# buckconvertervrs.net
KiCad netlist of a schematic drawn in EAGLE
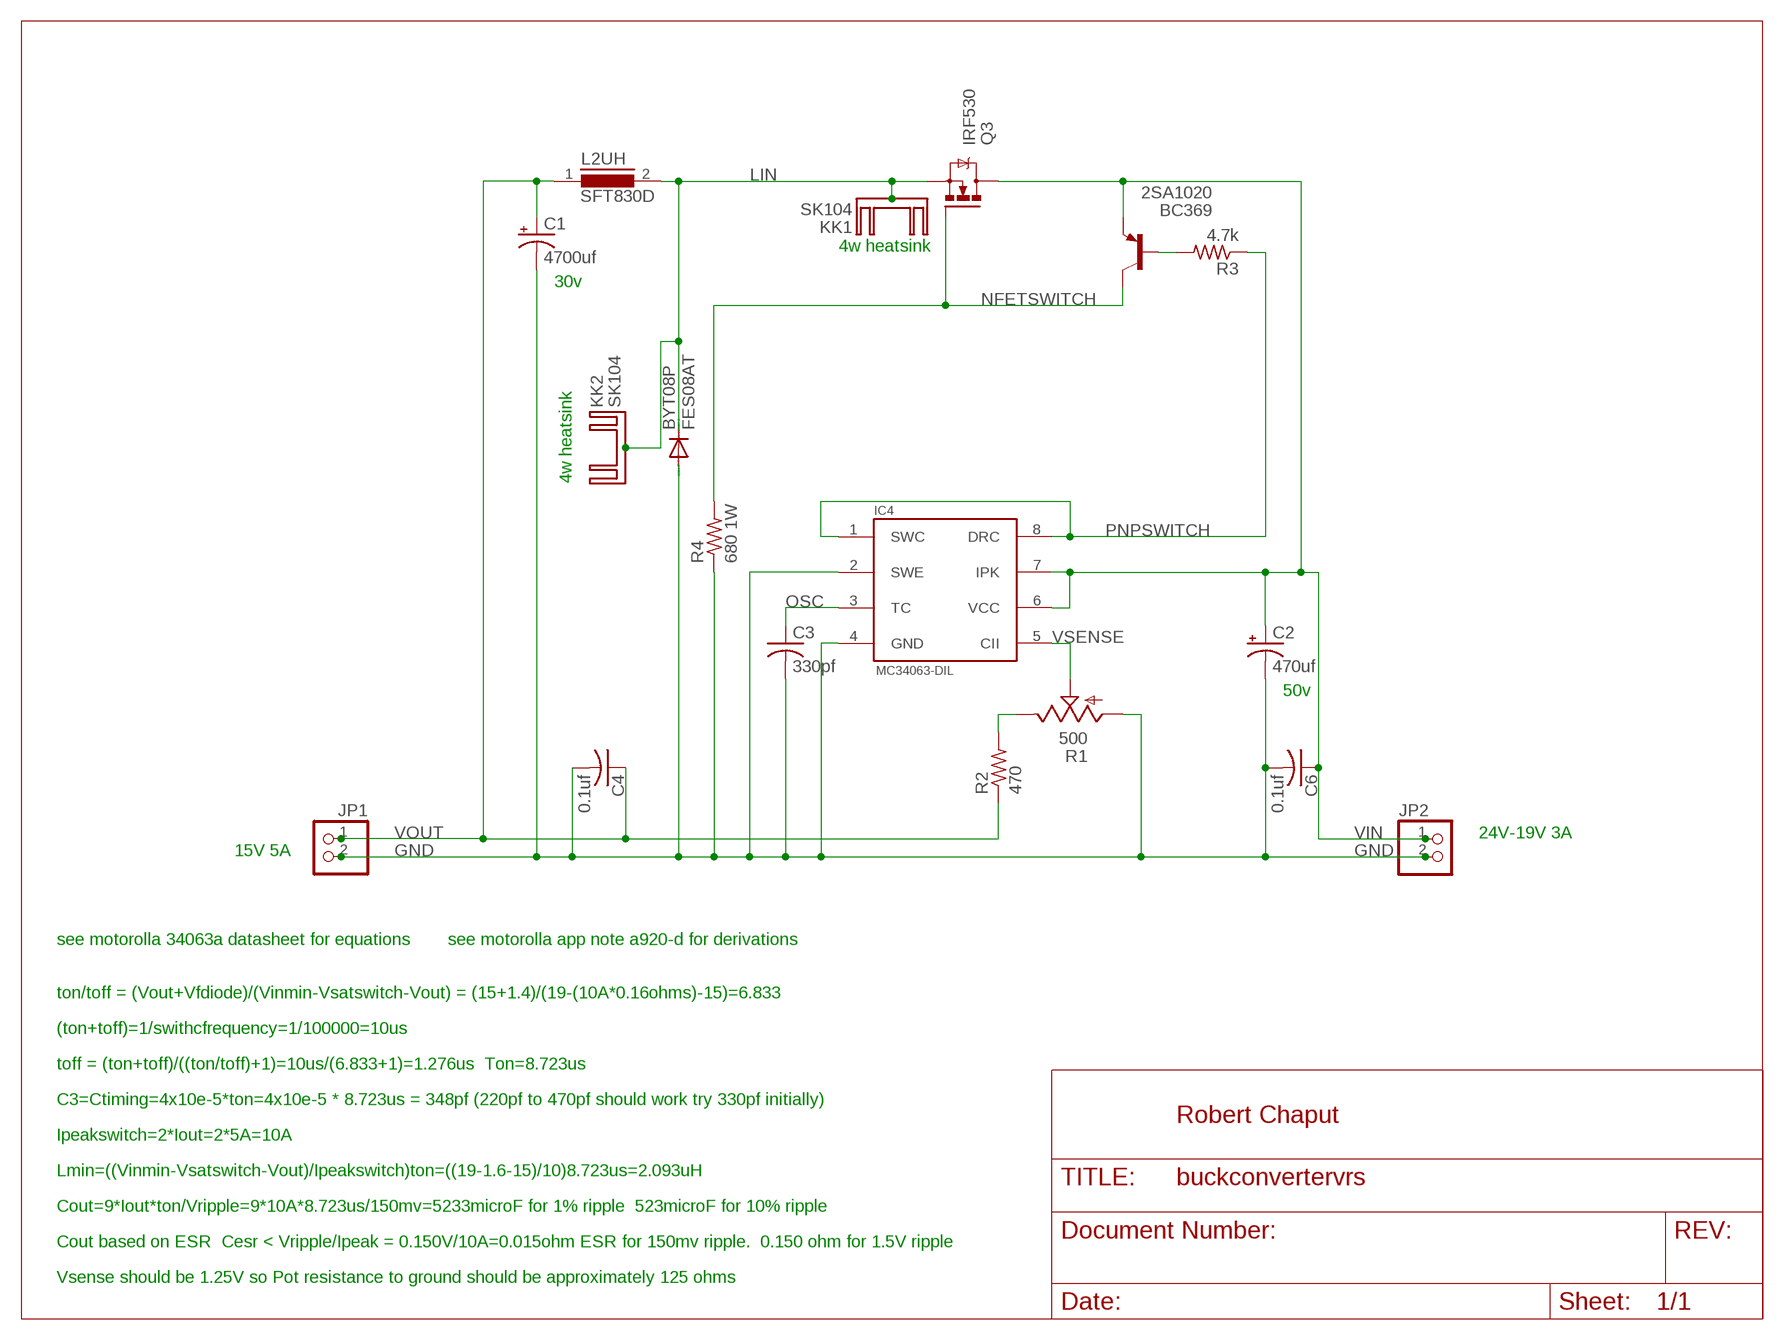
[diagram p0: schematic, sheet 1]

(export (version "E")
  (design (tool "Eeschema 10.0.6"))
  (components
    (comp (ref "2SA1020")
      (value "BC369")
      (footprint "eagle-import:TO92-BCE")
      (libsource (lib "eagle-import") (part "BC369"))
    )
    (comp (ref "BYT08P")
      (value "FES08AT")
      (footprint "eagle-import:DO220S")
      (libsource (lib "eagle-import") (part "FES08AT"))
    )
    (comp (ref "C1")
      (value "4700uf")
      (footprint "eagle-import:EB30D")
      (libsource (lib "eagle-import") (part "CPOL-USE10-30"))
    )
    (comp (ref "C2")
      (value "470uf")
      (footprint "eagle-import:E5-8,5")
      (libsource (lib "eagle-import") (part "CPOL-USE5-8.5"))
    )
    (comp (ref "C3")
      (value "330pf")
      (footprint "eagle-import:C050-030X075")
      (libsource (lib "eagle-import") (part "C-US050-030X075"))
    )
    (comp (ref "C4")
      (value "0.1uf")
      (footprint "eagle-import:C050-030X075")
      (libsource (lib "eagle-import") (part "C-US050-030X075"))
    )
    (comp (ref "C6")
      (value "0.1uf")
      (footprint "eagle-import:C050-030X075")
      (libsource (lib "eagle-import") (part "C-US050-030X075"))
    )
    (comp (ref "IC4")
      (value "MC34063-DIL")
      (footprint "eagle-import:DIL08")
      (libsource (lib "eagle-import") (part "MC34063-DIL"))
    )
    (comp (ref "JP1")
      (value "PINHD-1X2")
      (footprint "eagle-import:1X02")
      (libsource (lib "eagle-import") (part "PINHD-1X2"))
    )
    (comp (ref "JP2")
      (value "PINHD-1X2")
      (footprint "eagle-import:1X02")
      (libsource (lib "eagle-import") (part "PINHD-1X2"))
    )
    (comp (ref "KK1")
      (value "SK104")
      (footprint "eagle-import:SK104")
      (libsource (lib "eagle-import") (part "SK104"))
    )
    (comp (ref "KK2")
      (value "SK104")
      (footprint "eagle-import:SK104")
      (libsource (lib "eagle-import") (part "SK104"))
    )
    (comp (ref "L2UH")
      (value "SFT830D")
      (footprint "eagle-import:SFT830D")
      (libsource (lib "eagle-import") (part "SFT830D"))
    )
    (comp (ref "Q3")
      (value "IRF530")
      (footprint "eagle-import:TO220BV")
      (libsource (lib "eagle-import") (part "IRF530"))
    )
    (comp (ref "R1")
      (value "500")
      (footprint "eagle-import:PT-SPIN")
      (libsource (lib "eagle-import") (part "TRIM_US-PTSPIN"))
    )
    (comp (ref "R2")
      (value "470")
      (footprint "eagle-import:0309V")
      (libsource (lib "eagle-import") (part "R-US_0309/V"))
    )
    (comp (ref "R3")
      (value "4.7k")
      (footprint "eagle-import:0309V")
      (libsource (lib "eagle-import") (part "R-US_0309/V"))
    )
    (comp (ref "R4")
      (value "680 1W")
      (footprint "eagle-import:P0613V")
      (libsource (lib "eagle-import") (part "R-US_0613/5V"))
    )
  )
  (nets
    (net (code "1") (name "/GND") (class "Default")
      (node (ref "BYT08P") (pin "A") (pinfunction "A_A") (pintype "passive"))
      (node (ref "C1") (pin "-") (pinfunction "-_-") (pintype "passive"))
      (node (ref "C2") (pin "-") (pinfunction "-_-") (pintype "passive"))
      (node (ref "C3") (pin "2") (pinfunction "2_2") (pintype "passive"))
      (node (ref "C4") (pin "2") (pinfunction "2_2") (pintype "passive"))
      (node (ref "C6") (pin "2") (pinfunction "2_2") (pintype "passive"))
      (node (ref "IC4") (pin "2") (pinfunction "SWE_2") (pintype "bidirectional"))
      (node (ref "IC4") (pin "4") (pinfunction "GND_4") (pintype "power_in"))
      (node (ref "JP1") (pin "2") (pinfunction "2_2") (pintype "passive"))
      (node (ref "JP2") (pin "2") (pinfunction "2_2") (pintype "passive"))
      (node (ref "R1") (pin "A") (pinfunction "A_A") (pintype "passive"))
      (node (ref "R4") (pin "1") (pinfunction "1_1") (pintype "passive"))
    )
    (net (code "2") (name "/LIN") (class "Default")
      (node (ref "BYT08P") (pin "C") (pinfunction "C_C") (pintype "passive"))
      (node (ref "L2UH") (pin "2") (pinfunction "2_2") (pintype "passive"))
      (node (ref "Q3") (pin "S") (pinfunction "S_S") (pintype "passive"))
    )
    (net (code "3") (name "/NFETSWITCH") (class "Default")
      (node (ref "2SA1020") (pin "C") (pinfunction "C_C") (pintype "passive"))
      (node (ref "Q3") (pin "G") (pinfunction "G_G") (pintype "passive"))
      (node (ref "R4") (pin "2") (pinfunction "2_2") (pintype "passive"))
    )
    (net (code "4") (name "/OSC") (class "Default")
      (node (ref "C3") (pin "1") (pinfunction "1_1") (pintype "passive"))
      (node (ref "IC4") (pin "3") (pinfunction "TC_3") (pintype "bidirectional"))
    )
    (net (code "5") (name "/PNPSWITCH") (class "Default")
      (node (ref "IC4") (pin "1") (pinfunction "SWC_1") (pintype "bidirectional"))
      (node (ref "IC4") (pin "8") (pinfunction "DRC_8") (pintype "bidirectional"))
      (node (ref "R3") (pin "1") (pinfunction "1_1") (pintype "passive"))
    )
    (net (code "6") (name "/VIN") (class "Default")
      (node (ref "2SA1020") (pin "E") (pinfunction "E_E") (pintype "passive"))
      (node (ref "C2") (pin "+") (pinfunction "+_+") (pintype "passive"))
      (node (ref "C6") (pin "1") (pinfunction "1_1") (pintype "passive"))
      (node (ref "IC4") (pin "6") (pinfunction "VCC_6") (pintype "bidirectional"))
      (node (ref "IC4") (pin "7") (pinfunction "IPK_7") (pintype "bidirectional"))
      (node (ref "JP2") (pin "1") (pinfunction "1_1") (pintype "passive"))
      (node (ref "Q3") (pin "D") (pinfunction "D_D") (pintype "passive"))
    )
    (net (code "7") (name "/VOUT") (class "Default")
      (node (ref "C1") (pin "+") (pinfunction "+_+") (pintype "passive"))
      (node (ref "C4") (pin "1") (pinfunction "1_1") (pintype "passive"))
      (node (ref "JP1") (pin "1") (pinfunction "1_1") (pintype "passive"))
      (node (ref "L2UH") (pin "1") (pinfunction "1_1") (pintype "passive"))
      (node (ref "R2") (pin "1") (pinfunction "1_1") (pintype "passive"))
    )
    (net (code "8") (name "/VSENSE") (class "Default")
      (node (ref "IC4") (pin "5") (pinfunction "CII_5") (pintype "bidirectional"))
      (node (ref "R1") (pin "S") (pinfunction "S_S") (pintype "passive"))
    )
    (net (code "9") (name "Net-(2SA1020-PadB)") (class "Default")
      (node (ref "2SA1020") (pin "B") (pinfunction "B_B") (pintype "passive"))
      (node (ref "R3") (pin "2") (pinfunction "2_2") (pintype "passive"))
    )
    (net (code "10") (name "Net-(R1-PadE)") (class "Default")
      (node (ref "R1") (pin "E") (pinfunction "E_E") (pintype "passive"))
      (node (ref "R2") (pin "2") (pinfunction "2_2") (pintype "passive"))
    )
  )
)
